# rapidshark-lipo-charger-mk-1_0.net
KiCad netlist of a schematic drawn in EAGLE
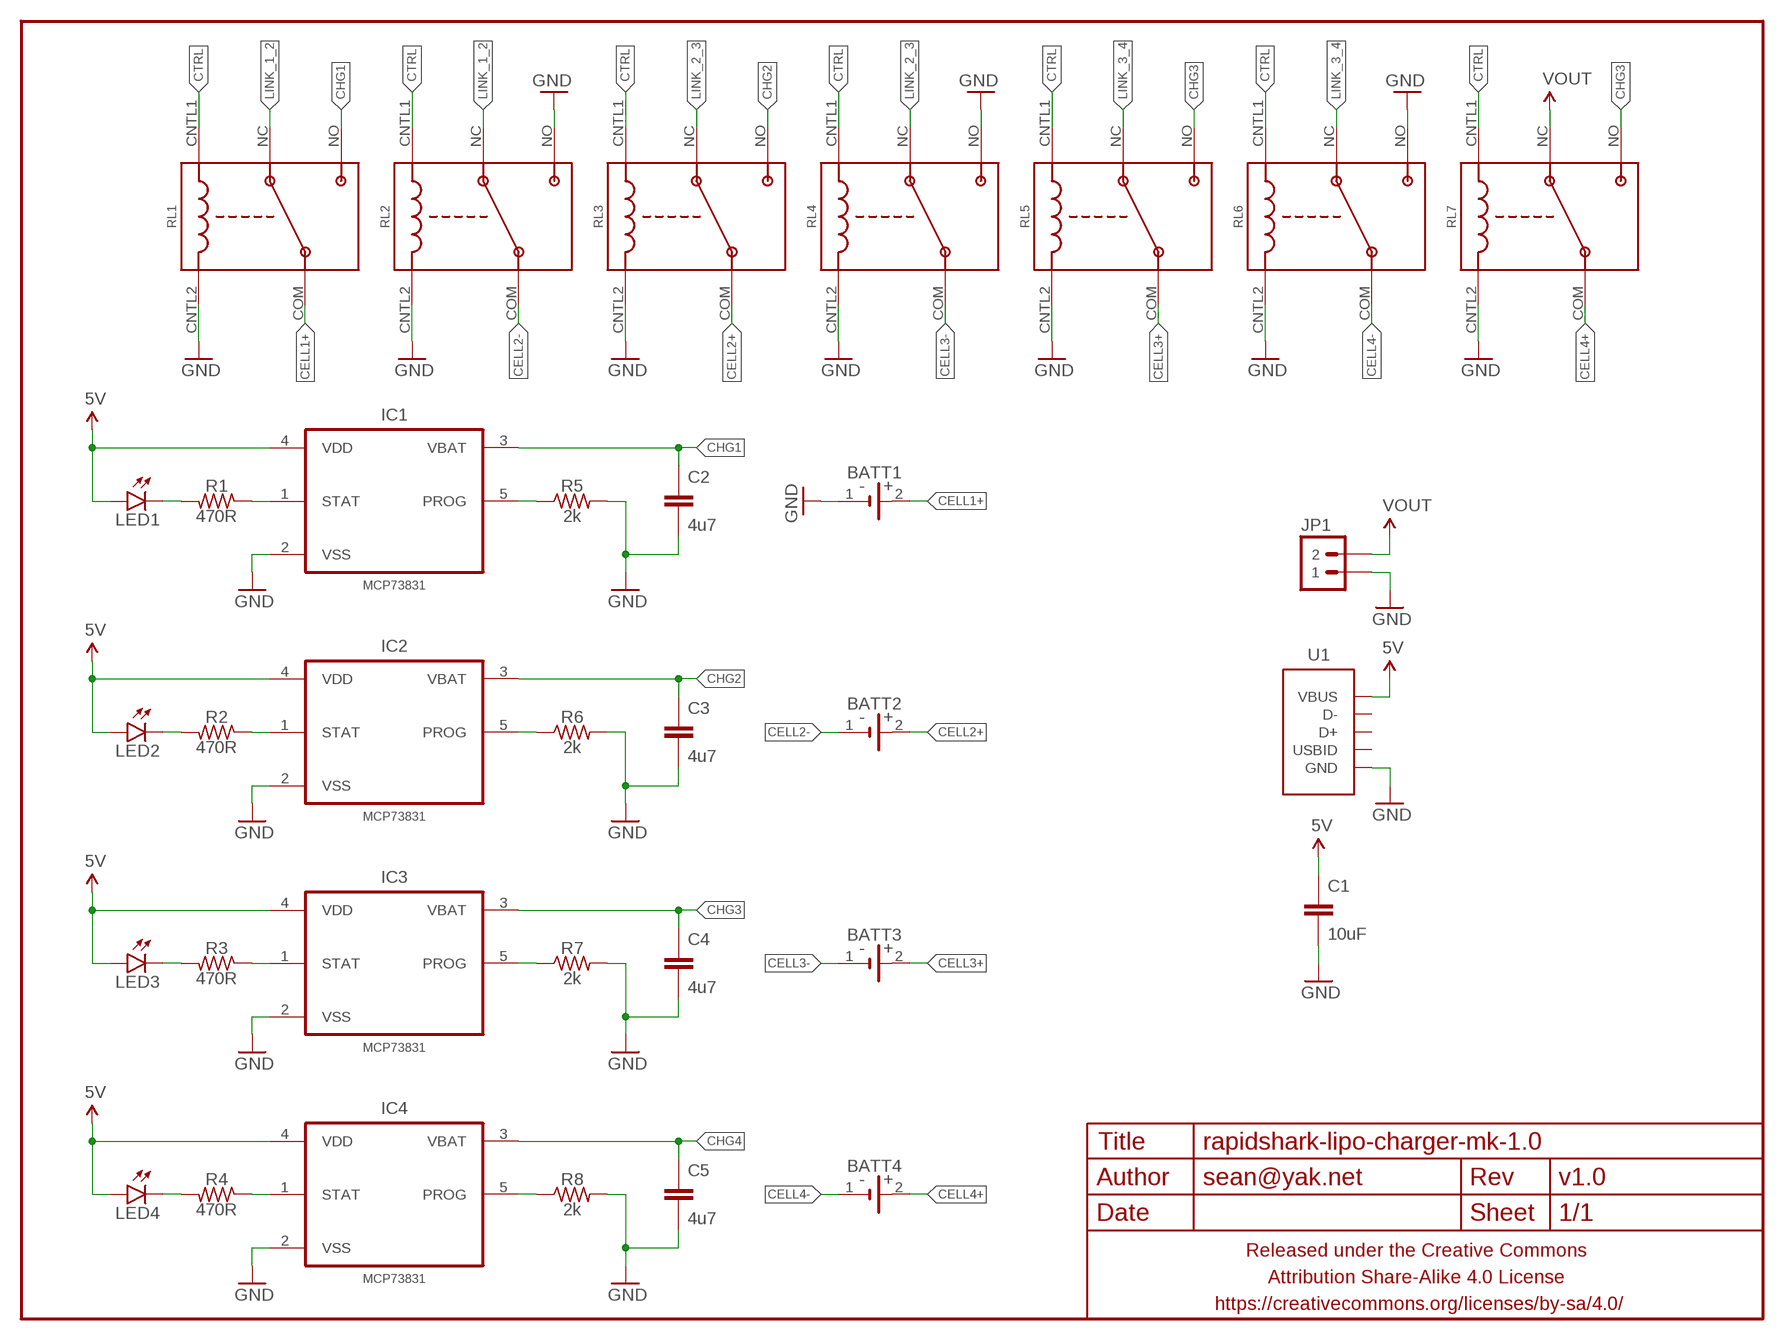
[diagram p0: schematic, sheet 1]

(export (version "E")
  (design (tool "Eeschema 10.0.6"))
  (components
    (comp (ref "BATT1")
      (value "LIPO1S_3.7V_EXT0.1IN_PTH")
      (footprint "eagle-import:1X02-CENTER-R+")
      (libsource (lib "eagle-import") (part "LIPO1S_3.7V_EXT0.1IN_PTH"))
    )
    (comp (ref "BATT2")
      (value "LIPO1S_3.7V_EXT0.1IN_PTH")
      (footprint "eagle-import:1X02-CENTER-R+")
      (libsource (lib "eagle-import") (part "LIPO1S_3.7V_EXT0.1IN_PTH"))
    )
    (comp (ref "BATT3")
      (value "LIPO1S_3.7V_EXT0.1IN_PTH")
      (footprint "eagle-import:1X02-CENTER-R+")
      (libsource (lib "eagle-import") (part "LIPO1S_3.7V_EXT0.1IN_PTH"))
    )
    (comp (ref "BATT4")
      (value "LIPO1S_3.7V_EXT0.1IN_PTH")
      (footprint "eagle-import:1X02-CENTER-R+")
      (libsource (lib "eagle-import") (part "LIPO1S_3.7V_EXT0.1IN_PTH"))
    )
    (comp (ref "C1")
      (value "10uF")
      (footprint "eagle-import:C0805")
      (libsource (lib "eagle-import") (part "CAPACITOR-CERAMICC0805"))
    )
    (comp (ref "C2")
      (value "4u7")
      (footprint "eagle-import:C0805")
      (libsource (lib "eagle-import") (part "CAPACITOR-CERAMICC0805"))
    )
    (comp (ref "C3")
      (value "4u7")
      (footprint "eagle-import:C0805")
      (libsource (lib "eagle-import") (part "CAPACITOR-CERAMICC0805"))
    )
    (comp (ref "C4")
      (value "4u7")
      (footprint "eagle-import:C0805")
      (libsource (lib "eagle-import") (part "CAPACITOR-CERAMICC0805"))
    )
    (comp (ref "C5")
      (value "4u7")
      (footprint "eagle-import:C0805")
      (libsource (lib "eagle-import") (part "CAPACITOR-CERAMICC0805"))
    )
    (comp (ref "FRAME1")
      (value "FRAME-LETTERNO_PACKAGE")
      (footprint "eagle-import:DUMMY")
      (fields (field (name "DESIGNER") "sean@yak.net") (field (name "VERSION") "v1.0"))
      (libsource (lib "eagle-import") (part "FRAME-LETTERNO_PACKAGE"))
    )
    (comp (ref "IC1")
      (value "MCP73831")
      (footprint "eagle-import:SOT95P280X145-5N")
      (fields (field (name "MPN") "MCP73831T-2ACI/OT"))
      (libsource (lib "eagle-import") (part "MCP73831T-2ACI/OT"))
    )
    (comp (ref "IC2")
      (value "MCP73831")
      (footprint "eagle-import:SOT95P280X145-5N")
      (fields (field (name "MPN") "MCP73831T-2ACI/OT"))
      (libsource (lib "eagle-import") (part "MCP73831T-2ACI/OT"))
    )
    (comp (ref "IC3")
      (value "MCP73831")
      (footprint "eagle-import:SOT95P280X145-5N")
      (fields (field (name "MPN") "MCP73831T-2ACI/OT"))
      (libsource (lib "eagle-import") (part "MCP73831T-2ACI/OT"))
    )
    (comp (ref "IC4")
      (value "MCP73831")
      (footprint "eagle-import:SOT95P280X145-5N")
      (fields (field (name "MPN") "MCP73831T-2ACI/OT"))
      (libsource (lib "eagle-import") (part "MCP73831T-2ACI/OT"))
    )
    (comp (ref "JP1")
      (value "M025MM")
      (footprint "eagle-import:SCREWTERMINAL-5MM-2")
      (libsource (lib "eagle-import") (part "M025MM"))
    )
    (comp (ref "LED1")
      (value "LED0805")
      (footprint "eagle-import:LED-0805")
      (libsource (lib "eagle-import") (part "LED0805"))
    )
    (comp (ref "LED2")
      (value "LED0805")
      (footprint "eagle-import:LED-0805")
      (libsource (lib "eagle-import") (part "LED0805"))
    )
    (comp (ref "LED3")
      (value "LED0805")
      (footprint "eagle-import:LED-0805")
      (libsource (lib "eagle-import") (part "LED0805"))
    )
    (comp (ref "LED4")
      (value "LED0805")
      (footprint "eagle-import:LED-0805")
      (libsource (lib "eagle-import") (part "LED0805"))
    )
    (comp (ref "R1")
      (value "470R")
      (footprint "eagle-import:R0805")
      (libsource (lib "eagle-import") (part "RESISTORR0805"))
    )
    (comp (ref "R2")
      (value "470R")
      (footprint "eagle-import:R0805")
      (libsource (lib "eagle-import") (part "RESISTORR0805"))
    )
    (comp (ref "R3")
      (value "470R")
      (footprint "eagle-import:R0805")
      (libsource (lib "eagle-import") (part "RESISTORR0805"))
    )
    (comp (ref "R4")
      (value "470R")
      (footprint "eagle-import:R0805")
      (libsource (lib "eagle-import") (part "RESISTORR0805"))
    )
    (comp (ref "R5")
      (value "2k")
      (footprint "eagle-import:R0805")
      (libsource (lib "eagle-import") (part "RESISTORR0805"))
    )
    (comp (ref "R6")
      (value "2k")
      (footprint "eagle-import:R0805")
      (libsource (lib "eagle-import") (part "RESISTORR0805"))
    )
    (comp (ref "R7")
      (value "2k")
      (footprint "eagle-import:R0805")
      (libsource (lib "eagle-import") (part "RESISTORR0805"))
    )
    (comp (ref "R8")
      (value "2k")
      (footprint "eagle-import:R0805")
      (libsource (lib "eagle-import") (part "RESISTORR0805"))
    )
    (comp (ref "RL1")
      (value "RELAY-SPDTMC25131")
      (footprint "eagle-import:RELAY-SPDT-MC25131")
      (libsource (lib "eagle-import") (part "RELAY-SPDTMC25131"))
    )
    (comp (ref "RL2")
      (value "RELAY-SPDTMC25131")
      (footprint "eagle-import:RELAY-SPDT-MC25131")
      (libsource (lib "eagle-import") (part "RELAY-SPDTMC25131"))
    )
    (comp (ref "RL3")
      (value "RELAY-SPDTMC25131")
      (footprint "eagle-import:RELAY-SPDT-MC25131")
      (libsource (lib "eagle-import") (part "RELAY-SPDTMC25131"))
    )
    (comp (ref "RL4")
      (value "RELAY-SPDTMC25131")
      (footprint "eagle-import:RELAY-SPDT-MC25131")
      (libsource (lib "eagle-import") (part "RELAY-SPDTMC25131"))
    )
    (comp (ref "RL5")
      (value "RELAY-SPDTMC25131")
      (footprint "eagle-import:RELAY-SPDT-MC25131")
      (libsource (lib "eagle-import") (part "RELAY-SPDTMC25131"))
    )
    (comp (ref "RL6")
      (value "RELAY-SPDTMC25131")
      (footprint "eagle-import:RELAY-SPDT-MC25131")
      (libsource (lib "eagle-import") (part "RELAY-SPDTMC25131"))
    )
    (comp (ref "RL7")
      (value "RELAY-SPDTMC25131")
      (footprint "eagle-import:RELAY-SPDT-MC25131")
      (libsource (lib "eagle-import") (part "RELAY-SPDTMC25131"))
    )
    (comp (ref "U1")
      (value "USB-ABFCI-10103594-USB-MICRO-B-LESS")
      (footprint "eagle-import:FCI-10103594-USB-MICRO-B-LESS")
      (libsource (lib "eagle-import") (part "USB-ABFCI-10103594-USB-MICRO-B-LESS"))
    )
  )
  (nets
    (net (code "1") (name "5V") (class "Default")
      (node (ref "C1") (pin "1") (pinfunction "1_1") (pintype "passive"))
      (node (ref "IC1") (pin "4") (pinfunction "VDD_4") (pintype "power_in"))
      (node (ref "IC2") (pin "4") (pinfunction "VDD_4") (pintype "power_in"))
      (node (ref "IC3") (pin "4") (pinfunction "VDD_4") (pintype "power_in"))
      (node (ref "IC4") (pin "4") (pinfunction "VDD_4") (pintype "power_in"))
      (node (ref "LED1") (pin "A") (pinfunction "A_A") (pintype "passive"))
      (node (ref "LED2") (pin "A") (pinfunction "A_A") (pintype "passive"))
      (node (ref "LED3") (pin "A") (pinfunction "A_A") (pintype "passive"))
      (node (ref "LED4") (pin "A") (pinfunction "A_A") (pintype "passive"))
      (node (ref "U1") (pin "1") (pinfunction "VBUS_1") (pintype "bidirectional"))
    )
    (net (code "2") (name "CELL1+") (class "Default")
      (node (ref "BATT1") (pin "2") (pinfunction "+_2") (pintype "passive"))
      (node (ref "RL1") (pin "COM") (pinfunction "COM_COM") (pintype "bidirectional"))
    )
    (net (code "3") (name "CELL2+") (class "Default")
      (node (ref "BATT2") (pin "2") (pinfunction "+_2") (pintype "passive"))
      (node (ref "RL3") (pin "COM") (pinfunction "COM_COM") (pintype "bidirectional"))
    )
    (net (code "4") (name "CELL2-") (class "Default")
      (node (ref "BATT2") (pin "1") (pinfunction "-_1") (pintype "passive"))
      (node (ref "RL2") (pin "COM") (pinfunction "COM_COM") (pintype "bidirectional"))
    )
    (net (code "5") (name "CELL3+") (class "Default")
      (node (ref "BATT3") (pin "2") (pinfunction "+_2") (pintype "passive"))
      (node (ref "RL5") (pin "COM") (pinfunction "COM_COM") (pintype "bidirectional"))
    )
    (net (code "6") (name "CELL3-") (class "Default")
      (node (ref "BATT3") (pin "1") (pinfunction "-_1") (pintype "passive"))
      (node (ref "RL4") (pin "COM") (pinfunction "COM_COM") (pintype "bidirectional"))
    )
    (net (code "7") (name "CELL4+") (class "Default")
      (node (ref "BATT4") (pin "2") (pinfunction "+_2") (pintype "passive"))
      (node (ref "RL7") (pin "COM") (pinfunction "COM_COM") (pintype "bidirectional"))
    )
    (net (code "8") (name "CELL4-") (class "Default")
      (node (ref "BATT4") (pin "1") (pinfunction "-_1") (pintype "passive"))
      (node (ref "RL6") (pin "COM") (pinfunction "COM_COM") (pintype "bidirectional"))
    )
    (net (code "9") (name "CHG1") (class "Default")
      (node (ref "C2") (pin "1") (pinfunction "1_1") (pintype "passive"))
      (node (ref "IC1") (pin "3") (pinfunction "VBAT_3") (pintype "output"))
      (node (ref "RL1") (pin "NO") (pinfunction "NO_NO") (pintype "bidirectional"))
    )
    (net (code "10") (name "CHG2") (class "Default")
      (node (ref "C3") (pin "1") (pinfunction "1_1") (pintype "passive"))
      (node (ref "IC2") (pin "3") (pinfunction "VBAT_3") (pintype "output"))
      (node (ref "RL3") (pin "NO") (pinfunction "NO_NO") (pintype "bidirectional"))
    )
    (net (code "11") (name "CHG3") (class "Default")
      (node (ref "C4") (pin "1") (pinfunction "1_1") (pintype "passive"))
      (node (ref "IC3") (pin "3") (pinfunction "VBAT_3") (pintype "output"))
      (node (ref "RL5") (pin "NO") (pinfunction "NO_NO") (pintype "bidirectional"))
      (node (ref "RL7") (pin "NO") (pinfunction "NO_NO") (pintype "bidirectional"))
    )
    (net (code "12") (name "CHG4") (class "Default")
      (node (ref "C5") (pin "1") (pinfunction "1_1") (pintype "passive"))
      (node (ref "IC4") (pin "3") (pinfunction "VBAT_3") (pintype "output"))
    )
    (net (code "13") (name "CTRL") (class "Default")
      (node (ref "RL1") (pin "CNTL1") (pinfunction "C$1_CNTL1") (pintype "bidirectional"))
      (node (ref "RL2") (pin "CNTL1") (pinfunction "C$1_CNTL1") (pintype "bidirectional"))
      (node (ref "RL3") (pin "CNTL1") (pinfunction "C$1_CNTL1") (pintype "bidirectional"))
      (node (ref "RL4") (pin "CNTL1") (pinfunction "C$1_CNTL1") (pintype "bidirectional"))
      (node (ref "RL5") (pin "CNTL1") (pinfunction "C$1_CNTL1") (pintype "bidirectional"))
      (node (ref "RL6") (pin "CNTL1") (pinfunction "C$1_CNTL1") (pintype "bidirectional"))
      (node (ref "RL7") (pin "CNTL1") (pinfunction "C$1_CNTL1") (pintype "bidirectional"))
    )
    (net (code "14") (name "GND") (class "Default")
      (node (ref "BATT1") (pin "1") (pinfunction "-_1") (pintype "passive"))
      (node (ref "C1") (pin "2") (pinfunction "2_2") (pintype "passive"))
      (node (ref "C2") (pin "2") (pinfunction "2_2") (pintype "passive"))
      (node (ref "C3") (pin "2") (pinfunction "2_2") (pintype "passive"))
      (node (ref "C4") (pin "2") (pinfunction "2_2") (pintype "passive"))
      (node (ref "C5") (pin "2") (pinfunction "2_2") (pintype "passive"))
      (node (ref "IC1") (pin "2") (pinfunction "VSS_2") (pintype "power_in"))
      (node (ref "IC2") (pin "2") (pinfunction "VSS_2") (pintype "power_in"))
      (node (ref "IC3") (pin "2") (pinfunction "VSS_2") (pintype "power_in"))
      (node (ref "IC4") (pin "2") (pinfunction "VSS_2") (pintype "power_in"))
      (node (ref "JP1") (pin "1") (pinfunction "1_1") (pintype "passive"))
      (node (ref "R5") (pin "2") (pinfunction "2_2") (pintype "passive"))
      (node (ref "R6") (pin "2") (pinfunction "2_2") (pintype "passive"))
      (node (ref "R7") (pin "2") (pinfunction "2_2") (pintype "passive"))
      (node (ref "R8") (pin "2") (pinfunction "2_2") (pintype "passive"))
      (node (ref "RL1") (pin "CNTL2") (pinfunction "C$2_CNTL2") (pintype "bidirectional"))
      (node (ref "RL2") (pin "CNTL2") (pinfunction "C$2_CNTL2") (pintype "bidirectional"))
      (node (ref "RL2") (pin "NO") (pinfunction "NO_NO") (pintype "bidirectional"))
      (node (ref "RL3") (pin "CNTL2") (pinfunction "C$2_CNTL2") (pintype "bidirectional"))
      (node (ref "RL4") (pin "CNTL2") (pinfunction "C$2_CNTL2") (pintype "bidirectional"))
      (node (ref "RL4") (pin "NO") (pinfunction "NO_NO") (pintype "bidirectional"))
      (node (ref "RL5") (pin "CNTL2") (pinfunction "C$2_CNTL2") (pintype "bidirectional"))
      (node (ref "RL6") (pin "CNTL2") (pinfunction "C$2_CNTL2") (pintype "bidirectional"))
      (node (ref "RL6") (pin "NO") (pinfunction "NO_NO") (pintype "bidirectional"))
      (node (ref "RL7") (pin "CNTL2") (pinfunction "C$2_CNTL2") (pintype "bidirectional"))
      (node (ref "U1") (pin "5") (pinfunction "GND_5") (pintype "bidirectional"))
    )
    (net (code "15") (name "LINK_1_2") (class "Default")
      (node (ref "RL1") (pin "NC") (pinfunction "NC_NC") (pintype "bidirectional"))
      (node (ref "RL2") (pin "NC") (pinfunction "NC_NC") (pintype "bidirectional"))
    )
    (net (code "16") (name "LINK_2_3") (class "Default")
      (node (ref "RL3") (pin "NC") (pinfunction "NC_NC") (pintype "bidirectional"))
      (node (ref "RL4") (pin "NC") (pinfunction "NC_NC") (pintype "bidirectional"))
    )
    (net (code "17") (name "LINK_3_4") (class "Default")
      (node (ref "RL5") (pin "NC") (pinfunction "NC_NC") (pintype "bidirectional"))
      (node (ref "RL6") (pin "NC") (pinfunction "NC_NC") (pintype "bidirectional"))
    )
    (net (code "18") (name "Net-(IC1-PROG)") (class "Default")
      (node (ref "IC1") (pin "5") (pinfunction "PROG_5") (pintype "input"))
      (node (ref "R5") (pin "1") (pinfunction "1_1") (pintype "passive"))
    )
    (net (code "19") (name "Net-(IC1-STAT)") (class "Default")
      (node (ref "IC1") (pin "1") (pinfunction "STAT_1") (pintype "output"))
      (node (ref "R1") (pin "1") (pinfunction "1_1") (pintype "passive"))
    )
    (net (code "20") (name "Net-(IC2-PROG)") (class "Default")
      (node (ref "IC2") (pin "5") (pinfunction "PROG_5") (pintype "input"))
      (node (ref "R6") (pin "1") (pinfunction "1_1") (pintype "passive"))
    )
    (net (code "21") (name "Net-(IC2-STAT)") (class "Default")
      (node (ref "IC2") (pin "1") (pinfunction "STAT_1") (pintype "output"))
      (node (ref "R2") (pin "1") (pinfunction "1_1") (pintype "passive"))
    )
    (net (code "22") (name "Net-(IC3-PROG)") (class "Default")
      (node (ref "IC3") (pin "5") (pinfunction "PROG_5") (pintype "input"))
      (node (ref "R7") (pin "1") (pinfunction "1_1") (pintype "passive"))
    )
    (net (code "23") (name "Net-(IC3-STAT)") (class "Default")
      (node (ref "IC3") (pin "1") (pinfunction "STAT_1") (pintype "output"))
      (node (ref "R3") (pin "1") (pinfunction "1_1") (pintype "passive"))
    )
    (net (code "24") (name "Net-(IC4-PROG)") (class "Default")
      (node (ref "IC4") (pin "5") (pinfunction "PROG_5") (pintype "input"))
      (node (ref "R8") (pin "1") (pinfunction "1_1") (pintype "passive"))
    )
    (net (code "25") (name "Net-(IC4-STAT)") (class "Default")
      (node (ref "IC4") (pin "1") (pinfunction "STAT_1") (pintype "output"))
      (node (ref "R4") (pin "1") (pinfunction "1_1") (pintype "passive"))
    )
    (net (code "26") (name "Net-(LED1-PadC)") (class "Default")
      (node (ref "LED1") (pin "C") (pinfunction "C_C") (pintype "passive"))
      (node (ref "R1") (pin "2") (pinfunction "2_2") (pintype "passive"))
    )
    (net (code "27") (name "Net-(LED2-PadC)") (class "Default")
      (node (ref "LED2") (pin "C") (pinfunction "C_C") (pintype "passive"))
      (node (ref "R2") (pin "2") (pinfunction "2_2") (pintype "passive"))
    )
    (net (code "28") (name "Net-(LED3-PadC)") (class "Default")
      (node (ref "LED3") (pin "C") (pinfunction "C_C") (pintype "passive"))
      (node (ref "R3") (pin "2") (pinfunction "2_2") (pintype "passive"))
    )
    (net (code "29") (name "Net-(LED4-PadC)") (class "Default")
      (node (ref "LED4") (pin "C") (pinfunction "C_C") (pintype "passive"))
      (node (ref "R4") (pin "2") (pinfunction "2_2") (pintype "passive"))
    )
    (net (code "30") (name "VOUT") (class "Default")
      (node (ref "JP1") (pin "2") (pinfunction "2_2") (pintype "passive"))
      (node (ref "RL7") (pin "NC") (pinfunction "NC_NC") (pintype "bidirectional"))
    )
    (net (code "31") (name "unconnected-(U1-D+-Pad3)") (class "Default")
      (node (ref "U1") (pin "3") (pinfunction "D+_3") (pintype "bidirectional"))
    )
    (net (code "32") (name "unconnected-(U1-D--Pad2)") (class "Default")
      (node (ref "U1") (pin "2") (pinfunction "D-_2") (pintype "bidirectional"))
    )
    (net (code "33") (name "unconnected-(U1-USBID-Pad4)") (class "Default")
      (node (ref "U1") (pin "4") (pinfunction "USBID_4") (pintype "bidirectional"))
    )
  )
)
